# PROC099B_LDO.net
KiCad netlist of a schematic drawn in Altium Designer
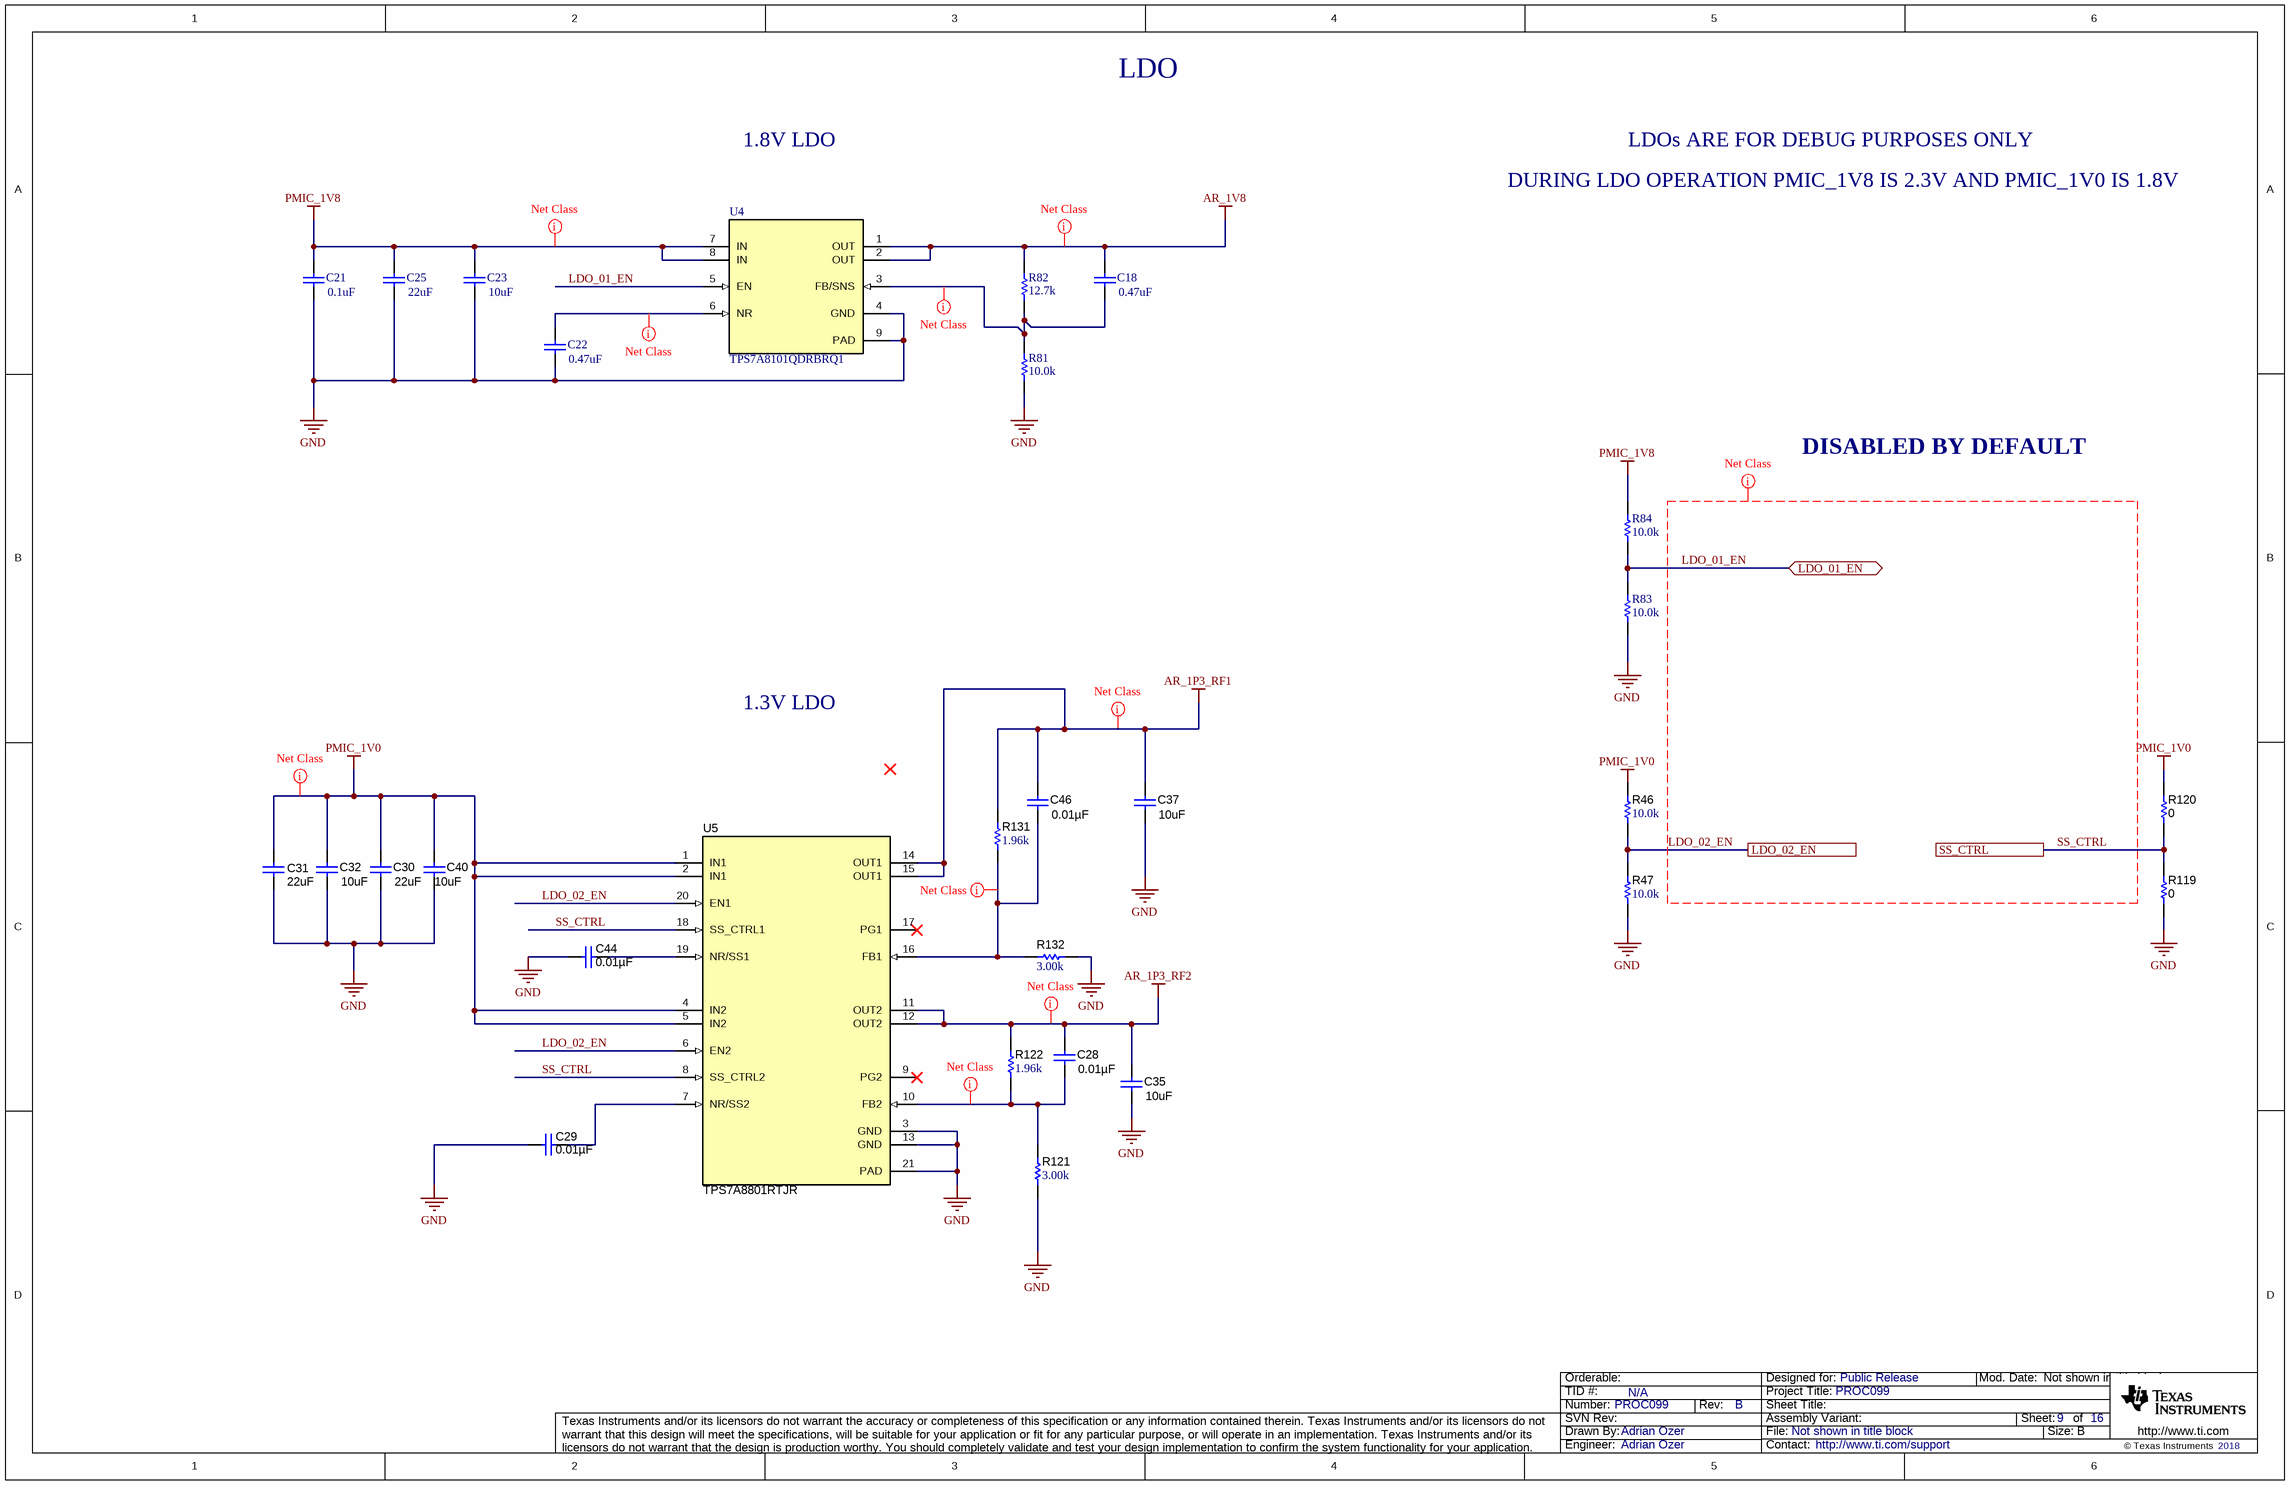
[diagram p0: PROC099B_LDO.SchDoc]

(export (version "E")
  (design (tool "Eeschema 10.0.6"))
  (components
    (comp (ref "C18")
      (value "GCM188R71C474KA55D")
      (footprint "0603")
      (description "CAP, CERM, 0.47 uF, 16 V, +/- 10%, X7R, AEC-Q200 Grade 1, 0603")
      (fields
        (field (name "MANUFACTURER") "MuRata")
        (field (name "VALUEDISPLAYED") "0.47uF")
        (field (name "PUBLISHER") "Texas Instruments")
      )
      (libsource (lib "Altium Vault - TI") (part "Capacitor"))
    )
    (comp (ref "C21")
      (value "CGA2B3X7R1H104K050BB")
      (footprint "0402")
      (description "CAP, CERM, 0.1 uF, 50 V, +/- 10%, X7R, AEC-Q200 Grade 1, 0402")
      (fields
        (field (name "MANUFACTURER") "TDK")
        (field (name "VALUEDISPLAYED") "0.1uF")
        (field (name "PUBLISHER") "Texas Instruments")
      )
      (libsource (lib "Altium Vault - TI") (part "Capacitor"))
    )
    (comp (ref "C22")
      (value "GCM188R71C474KA55D")
      (footprint "0603")
      (description "CAP, CERM, 0.47 uF, 16 V, +/- 10%, X7R, AEC-Q200 Grade 1, 0603")
      (fields
        (field (name "MANUFACTURER") "MuRata")
        (field (name "VALUEDISPLAYED") "0.47uF")
        (field (name "PUBLISHER") "Texas Instruments")
      )
      (libsource (lib "Altium Vault - TI") (part "Capacitor"))
    )
    (comp (ref "C23")
      (value "GCM21BR71A106KE22L")
      (footprint "0805_HV")
      (description "CAP, CERM, 10 uF, 10 V, +/- 10%, X7R, 0805")
      (fields
        (field (name "MANUFACTURER") "MuRata")
        (field (name "VALUEDISPLAYED") "10uF")
        (field (name "PUBLISHER") "Texas Instruments")
      )
      (libsource (lib "Altium Vault - TI") (part "Capacitor"))
    )
    (comp (ref "C25")
      (value "CGA5L1X7R0J226M160AC")
      (footprint "1206_180")
      (description "CAP, CERM, 22 uF, 6.3 V, +/- 10%, X7R, AEC-Q200 Grade 1, 1206")
      (fields
        (field (name "MANUFACTURER") "TDK")
        (field (name "VALUEDISPLAYED") "22uF")
        (field (name "PUBLISHER") "Texas Instruments")
      )
      (libsource (lib "Altium Vault - TI") (part "Capacitor"))
    )
    (comp (ref "C28")
      (value "CGA2B3X8R1H103K050BB")
      (footprint "0402L")
      (description "CAP, CERM, 0.01 µF, 50 V,+/- 10%, X8R, AEC-Q200 Grade 0, 0402")
      (fields (field (name "MANUFACTURER") "TDK") (field (name "VALUEDISPLAYED") "0.01µF"))
      (libsource (lib "Altium Vault - TI") (part "Capacitor"))
    )
    (comp (ref "C29")
      (value "CGA2B3X8R1H103K050BB")
      (footprint "0402L")
      (description "CAP, CERM, 0.01 µF, 50 V,+/- 10%, X8R, AEC-Q200 Grade 0, 0402")
      (fields (field (name "MANUFACTURER") "TDK") (field (name "VALUEDISPLAYED") "0.01µF"))
      (libsource (lib "Altium Vault - TI") (part "Capacitor"))
    )
    (comp (ref "C30")
      (value "CGA5L1X7R0J226M160AC")
      (footprint "1206_180")
      (description "CAP, CERM, 22 uF, 6.3 V, +/- 10%, X7R, AEC-Q200 Grade 1, 1206")
      (fields
        (field (name "MANUFACTURER") "TDK")
        (field (name "VALUEDISPLAYED") "22uF")
        (field (name "PUBLISHER") "Texas Instruments")
      )
      (libsource (lib "Altium Vault - TI") (part "Capacitor"))
    )
    (comp (ref "C31")
      (value "CGA5L1X7R0J226M160AC")
      (footprint "1206_180")
      (description "CAP, CERM, 22 uF, 6.3 V, +/- 10%, X7R, AEC-Q200 Grade 1, 1206")
      (fields
        (field (name "MANUFACTURER") "TDK")
        (field (name "VALUEDISPLAYED") "22uF")
        (field (name "PUBLISHER") "Texas Instruments")
      )
      (libsource (lib "Altium Vault - TI") (part "Capacitor"))
    )
    (comp (ref "C32")
      (value "GCM21BR71A106KE22L")
      (footprint "0805")
      (description "CAP, CERM, 10 uF, 10 V, +/- 10%, X7R, 0805")
      (fields
        (field (name "MANUFACTURER") "MuRata")
        (field (name "VALUEDISPLAYED") "10uF")
        (field (name "PUBLISHER") "Texas Instruments")
      )
      (libsource (lib "Altium Vault - TI") (part "CMP-0008017-2"))
    )
    (comp (ref "C35")
      (value "GCM21BR71A106KE22L")
      (footprint "0805_HV")
      (description "CAP, CERM, 10 uF, 10 V, +/- 10%, X7R, 0805")
      (fields
        (field (name "MANUFACTURER") "MuRata")
        (field (name "VALUEDISPLAYED") "10uF")
        (field (name "PUBLISHER") "Texas Instruments")
      )
      (libsource (lib "Altium Vault - TI") (part "CMP-0008017-2"))
    )
    (comp (ref "C37")
      (value "GCM21BR71A106KE22L")
      (footprint "0805_HV")
      (description "CAP, CERM, 10 uF, 10 V, +/- 10%, X7R, 0805")
      (fields
        (field (name "MANUFACTURER") "MuRata")
        (field (name "VALUEDISPLAYED") "10uF")
        (field (name "PUBLISHER") "Texas Instruments")
      )
      (libsource (lib "Altium Vault - TI") (part "CMP-0008017-2"))
    )
    (comp (ref "C40")
      (value "GCM21BR71A106KE22L")
      (footprint "0805_HV1")
      (description "CAP, CERM, 10 uF, 10 V, +/- 10%, X7R, 0805")
      (fields
        (field (name "MANUFACTURER") "MuRata")
        (field (name "VALUEDISPLAYED") "10uF")
        (field (name "PUBLISHER") "Texas Instruments")
      )
      (libsource (lib "Altium Vault - TI") (part "CMP-0008017-2"))
    )
    (comp (ref "C44")
      (value "CGA2B3X8R1H103K050BB")
      (footprint "0402L")
      (description "CAP, CERM, 0.01 µF, 50 V,+/- 10%, X8R, AEC-Q200 Grade 0, 0402")
      (fields (field (name "MANUFACTURER") "TDK") (field (name "VALUEDISPLAYED") "0.01µF"))
      (libsource (lib "Altium Vault - TI") (part "Capacitor"))
    )
    (comp (ref "C46")
      (value "CGA2B3X8R1H103K050BB")
      (footprint "0402L")
      (description "CAP, CERM, 0.01 µF, 50 V,+/- 10%, X8R, AEC-Q200 Grade 0, 0402")
      (fields (field (name "MANUFACTURER") "TDK") (field (name "VALUEDISPLAYED") "0.01µF"))
      (libsource (lib "Altium Vault - TI") (part "Capacitor"))
    )
    (comp (ref "R46")
      (value "CRCW040210K0FKED")
      (footprint "0402L")
      (description "RES, 10.0 k, 1%, 0.063 W, AEC-Q200 Grade 0, 0402")
      (fields (field (name "MANUFACTURER") "Vishay-Dale") (field (name "VALUEDISPLAYED") "10.0k"))
      (libsource (lib "Altium Vault - TI") (part "Resistor"))
    )
    (comp (ref "R47")
      (value "CRCW040210K0FKED")
      (footprint "0402L")
      (description "RES, 10.0 k, 1%, 0.063 W, AEC-Q200 Grade 0, 0402")
      (fields (field (name "MANUFACTURER") "Vishay-Dale") (field (name "VALUEDISPLAYED") "10.0k"))
      (libsource (lib "Altium Vault - TI") (part "Resistor"))
    )
    (comp (ref "R81")
      (value "CRCW040210K0FKED")
      (footprint "0402L")
      (description "RES, 10.0 k, 1%, 0.063 W, AEC-Q200 Grade 0, 0402")
      (fields (field (name "MANUFACTURER") "Vishay-Dale") (field (name "VALUEDISPLAYED") "10.0k"))
      (libsource (lib "Altium Vault - TI") (part "CMP-0025958-3"))
    )
    (comp (ref "R82")
      (value "CRCW040212K7FKED")
      (footprint "0402L")
      (description "RES, 12.7 k, 1%, 0.063 W, AEC-Q200 Grade 0, 0402")
      (fields (field (name "MANUFACTURER") "Vishay-Dale") (field (name "VALUEDISPLAYED") "12.7k"))
      (libsource (lib "Altium Vault - TI") (part "CMP-0025993-3"))
    )
    (comp (ref "R83")
      (value "CRCW040210K0FKED")
      (footprint "0402")
      (description "RES, 10.0 k, 1%, 0.063 W, AEC-Q200 Grade 0, 0402")
      (fields (field (name "MANUFACTURER") "Vishay-Dale") (field (name "VALUEDISPLAYED") "10.0k"))
      (libsource (lib "Altium Vault - TI") (part "Resistor"))
    )
    (comp (ref "R84")
      (value "CRCW040210K0FKED")
      (footprint "0402")
      (description "RES, 10.0 k, 1%, 0.063 W, AEC-Q200 Grade 0, 0402")
      (fields (field (name "MANUFACTURER") "Vishay-Dale") (field (name "VALUEDISPLAYED") "10.0k"))
      (libsource (lib "Altium Vault - TI") (part "Resistor"))
    )
    (comp (ref "R119")
      (value "ERJ-2GE0R00X")
      (footprint "0402L")
      (description "RES, 0, 5%, 0.063 W, 0402")
      (fields
        (field (name "MANUFACTURER") "Panasonic")
        (field (name "VALUEDISPLAYED") "0")
        (field (name "PUBLISHER") "Texas Instruments")
      )
      (libsource (lib "Altium Vault - TI") (part "Resistor"))
    )
    (comp (ref "R120")
      (value "ERJ-2GE0R00X")
      (footprint "0402L")
      (description "RES, 0, 5%, 0.063 W, 0402")
      (fields
        (field (name "MANUFACTURER") "Panasonic")
        (field (name "VALUEDISPLAYED") "0")
        (field (name "PUBLISHER") "Texas Instruments")
      )
      (libsource (lib "Altium Vault - TI") (part "CMP-0026992-2"))
    )
    (comp (ref "R121")
      (value "CRCW04023K00FKED")
      (footprint "0402L")
      (description "RES, 3.00 k, 1%, 0.063 W, AEC-Q200 Grade 0, 0402")
      (fields (field (name "MANUFACTURER") "Vishay-Dale") (field (name "VALUEDISPLAYED") "3.00k"))
      (libsource (lib "Altium Vault - TI") (part "Resistor"))
    )
    (comp (ref "R122")
      (value "CRCW04021K96FKED")
      (footprint "0402L")
      (description "RES, 1.96 k, 1%, 0.063 W, AEC-Q200 Grade 0, 0402")
      (fields (field (name "MANUFACTURER") "Vishay-Dale") (field (name "VALUEDISPLAYED") "1.96k"))
      (libsource (lib "Altium Vault - TI") (part "Resistor"))
    )
    (comp (ref "R131")
      (value "CRCW04021K96FKED")
      (footprint "0402L")
      (description "RES, 1.96 k, 1%, 0.063 W, AEC-Q200 Grade 0, 0402")
      (fields (field (name "MANUFACTURER") "Vishay-Dale") (field (name "VALUEDISPLAYED") "1.96k"))
      (libsource (lib "Altium Vault - TI") (part "Resistor"))
    )
    (comp (ref "R132")
      (value "CRCW04023K00FKED")
      (footprint "0402L")
      (description "RES, 3.00 k, 1%, 0.063 W, AEC-Q200 Grade 0, 0402")
      (fields (field (name "MANUFACTURER") "Vishay-Dale") (field (name "VALUEDISPLAYED") "3.00k"))
      (libsource (lib "Altium Vault - TI") (part "Resistor"))
    )
    (comp (ref "U4")
      (value "TPS7A8101QDRBRQ1")
      (footprint "DRB0008A")
      (fields
        (field (name "MANUFACTURER") "Texas Instruments")
        (field (name "PARTNUMBER") "TPS7A8101QDRBRQ1")
        (field (name "PUBLISHER") "Texas Instruments")
      )
      (libsource (lib "Altium Vault - TI") (part "TPS7A80xx"))
    )
    (comp (ref "U5")
      (value "TPS7A8801RTJR")
      (footprint "RTJ0020D")
      (description "Dual, 1-A, Low Noise (3.8-uVRMS), LDO Voltage Regulator, RTJ0020D (WQFN-20)")
      (fields
        (field (name "ALTERNATE PARTNUMBER") "TPS7A8801RTJT")
        (field (name "MANUFACTURER") "Texas Instruments")
        (field (name "PARTNUMBER") "TPS7A8801RTJR")
        (field (name "PUBLISHER") "Texas Instruments")
      )
      (libsource (lib "Altium Vault - TI") (part "TPS7A8801"))
    )
  )
  (nets
    (net (code "1") (name "/LDO_01_EN") (class "Default")
      (node (ref "R83") (pin "2") (pinfunction "2_2") (pintype "passive"))
      (node (ref "R84") (pin "1") (pinfunction "1_1") (pintype "passive"))
      (node (ref "U4") (pin "5") (pinfunction "EN_5") (pintype "input"))
    )
    (net (code "2") (name "/LDO_02_EN") (class "Default")
      (node (ref "R46") (pin "2") (pinfunction "2_2") (pintype "passive"))
      (node (ref "R47") (pin "1") (pinfunction "1_1") (pintype "passive"))
      (node (ref "U5") (pin "20") (pinfunction "EN1_20") (pintype "input"))
      (node (ref "U5") (pin "6") (pinfunction "EN2_6") (pintype "input"))
    )
    (net (code "3") (name "/SS_CTRL") (class "Default")
      (node (ref "R119") (pin "2") (pinfunction "2_2") (pintype "passive"))
      (node (ref "R120") (pin "1") (pinfunction "1_1") (pintype "passive"))
      (node (ref "U5") (pin "18") (pinfunction "SS_CTRL1_18") (pintype "input"))
      (node (ref "U5") (pin "8") (pinfunction "SS_CTRL2_8") (pintype "input"))
    )
    (net (code "4") (name "AR_1P3_RF1") (class "Default")
      (node (ref "C37") (pin "2") (pinfunction "2_2") (pintype "passive"))
      (node (ref "C46") (pin "2") (pinfunction "2_2") (pintype "passive"))
      (node (ref "R131") (pin "2") (pinfunction "2_2") (pintype "passive"))
      (node (ref "U5") (pin "14") (pinfunction "OUT1_14") (pintype "power_in"))
      (node (ref "U5") (pin "15") (pinfunction "OUT1_15") (pintype "power_in"))
    )
    (net (code "5") (name "AR_1P3_RF2") (class "Default")
      (node (ref "C28") (pin "2") (pinfunction "2_2") (pintype "passive"))
      (node (ref "C35") (pin "2") (pinfunction "2_2") (pintype "passive"))
      (node (ref "R122") (pin "2") (pinfunction "2_2") (pintype "passive"))
      (node (ref "U5") (pin "11") (pinfunction "OUT2_11") (pintype "power_in"))
      (node (ref "U5") (pin "12") (pinfunction "OUT2_12") (pintype "power_in"))
    )
    (net (code "6") (name "AR_1V8") (class "Default")
      (node (ref "C18") (pin "1") (pinfunction "1_1") (pintype "passive"))
      (node (ref "R82") (pin "2") (pinfunction "2_2") (pintype "passive"))
      (node (ref "U4") (pin "1") (pinfunction "OUT_1") (pintype "power_in"))
      (node (ref "U4") (pin "2") (pinfunction "OUT_2") (pintype "power_in"))
    )
    (net (code "7") (name "GND") (class "Default")
      (node (ref "C21") (pin "2") (pinfunction "2_2") (pintype "passive"))
      (node (ref "C22") (pin "2") (pinfunction "2_2") (pintype "passive"))
      (node (ref "C23") (pin "2") (pinfunction "2_2") (pintype "passive"))
      (node (ref "C25") (pin "2") (pinfunction "2_2") (pintype "passive"))
      (node (ref "C29") (pin "1") (pinfunction "1_1") (pintype "passive"))
      (node (ref "C30") (pin "1") (pinfunction "1_1") (pintype "passive"))
      (node (ref "C31") (pin "1") (pinfunction "1_1") (pintype "passive"))
      (node (ref "C32") (pin "1") (pinfunction "1_1") (pintype "passive"))
      (node (ref "C35") (pin "1") (pinfunction "1_1") (pintype "passive"))
      (node (ref "C37") (pin "1") (pinfunction "1_1") (pintype "passive"))
      (node (ref "C40") (pin "1") (pinfunction "1_1") (pintype "passive"))
      (node (ref "C44") (pin "1") (pinfunction "1_1") (pintype "passive"))
      (node (ref "R119") (pin "1") (pinfunction "1_1") (pintype "passive"))
      (node (ref "R121") (pin "1") (pinfunction "1_1") (pintype "passive"))
      (node (ref "R132") (pin "1") (pinfunction "1_1") (pintype "passive"))
      (node (ref "R47") (pin "2") (pinfunction "2_2") (pintype "passive"))
      (node (ref "R81") (pin "1") (pinfunction "1_1") (pintype "passive"))
      (node (ref "R83") (pin "1") (pinfunction "1_1") (pintype "passive"))
      (node (ref "U4") (pin "4") (pinfunction "GND_4") (pintype "power_in"))
      (node (ref "U4") (pin "9") (pinfunction "PAD_9") (pintype "passive"))
      (node (ref "U5") (pin "13") (pinfunction "GND_13") (pintype "power_in"))
      (node (ref "U5") (pin "21") (pinfunction "PAD_21") (pintype "power_in"))
      (node (ref "U5") (pin "3") (pinfunction "GND_3") (pintype "power_in"))
    )
    (net (code "8") (name "Net-(U4-FB{slash}SNS)") (class "Default")
      (node (ref "C18") (pin "2") (pinfunction "2_2") (pintype "passive"))
      (node (ref "R81") (pin "2") (pinfunction "2_2") (pintype "passive"))
      (node (ref "R82") (pin "1") (pinfunction "1_1") (pintype "passive"))
      (node (ref "U4") (pin "3") (pinfunction "FB/SNS_3") (pintype "input"))
    )
    (net (code "9") (name "Net-(U4-NR)") (class "Default")
      (node (ref "C22") (pin "1") (pinfunction "1_1") (pintype "passive"))
      (node (ref "U4") (pin "6") (pinfunction "NR_6") (pintype "input"))
    )
    (net (code "10") (name "Net-(U5-FB1)") (class "Default")
      (node (ref "C46") (pin "1") (pinfunction "1_1") (pintype "passive"))
      (node (ref "R131") (pin "1") (pinfunction "1_1") (pintype "passive"))
      (node (ref "R132") (pin "2") (pinfunction "2_2") (pintype "passive"))
      (node (ref "U5") (pin "16") (pinfunction "FB1_16") (pintype "input"))
    )
    (net (code "11") (name "Net-(U5-FB2)") (class "Default")
      (node (ref "C28") (pin "1") (pinfunction "1_1") (pintype "passive"))
      (node (ref "R121") (pin "2") (pinfunction "2_2") (pintype "passive"))
      (node (ref "R122") (pin "1") (pinfunction "1_1") (pintype "passive"))
      (node (ref "U5") (pin "10") (pinfunction "FB2_10") (pintype "input"))
    )
    (net (code "12") (name "Net-(U5-NR{slash}SS1)") (class "Default")
      (node (ref "C44") (pin "2") (pinfunction "2_2") (pintype "passive"))
      (node (ref "U5") (pin "19") (pinfunction "NR/SS1_19") (pintype "input"))
    )
    (net (code "13") (name "Net-(U5-NR{slash}SS2)") (class "Default")
      (node (ref "C29") (pin "2") (pinfunction "2_2") (pintype "passive"))
      (node (ref "U5") (pin "7") (pinfunction "NR/SS2_7") (pintype "input"))
    )
    (net (code "14") (name "PMIC_1V0") (class "Default")
      (node (ref "C30") (pin "2") (pinfunction "2_2") (pintype "passive"))
      (node (ref "C31") (pin "2") (pinfunction "2_2") (pintype "passive"))
      (node (ref "C32") (pin "2") (pinfunction "2_2") (pintype "passive"))
      (node (ref "C40") (pin "2") (pinfunction "2_2") (pintype "passive"))
      (node (ref "R120") (pin "2") (pinfunction "2_2") (pintype "passive"))
      (node (ref "R46") (pin "1") (pinfunction "1_1") (pintype "passive"))
      (node (ref "U5") (pin "1") (pinfunction "IN1_1") (pintype "power_in"))
      (node (ref "U5") (pin "2") (pinfunction "IN1_2") (pintype "power_in"))
      (node (ref "U5") (pin "4") (pinfunction "IN2_4") (pintype "power_in"))
      (node (ref "U5") (pin "5") (pinfunction "IN2_5") (pintype "power_in"))
    )
    (net (code "15") (name "PMIC_1V8") (class "Default")
      (node (ref "C21") (pin "1") (pinfunction "1_1") (pintype "passive"))
      (node (ref "C23") (pin "1") (pinfunction "1_1") (pintype "passive"))
      (node (ref "C25") (pin "1") (pinfunction "1_1") (pintype "passive"))
      (node (ref "R84") (pin "2") (pinfunction "2_2") (pintype "passive"))
      (node (ref "U4") (pin "7") (pinfunction "IN_7") (pintype "power_in"))
      (node (ref "U4") (pin "8") (pinfunction "IN_8") (pintype "power_in"))
    )
    (net (code "16") (name "unconnected-(U5-PG1-Pad17)") (class "Default")
      (node (ref "U5") (pin "17") (pinfunction "PG1_17") (pintype "open_collector+no_connect"))
    )
    (net (code "17") (name "unconnected-(U5-PG2-Pad9)") (class "Default")
      (node (ref "U5") (pin "9") (pinfunction "PG2_9") (pintype "open_collector+no_connect"))
    )
  )
)
